# TopSheet_orig.net
KiCad netlist of a schematic drawn in Altium Designer
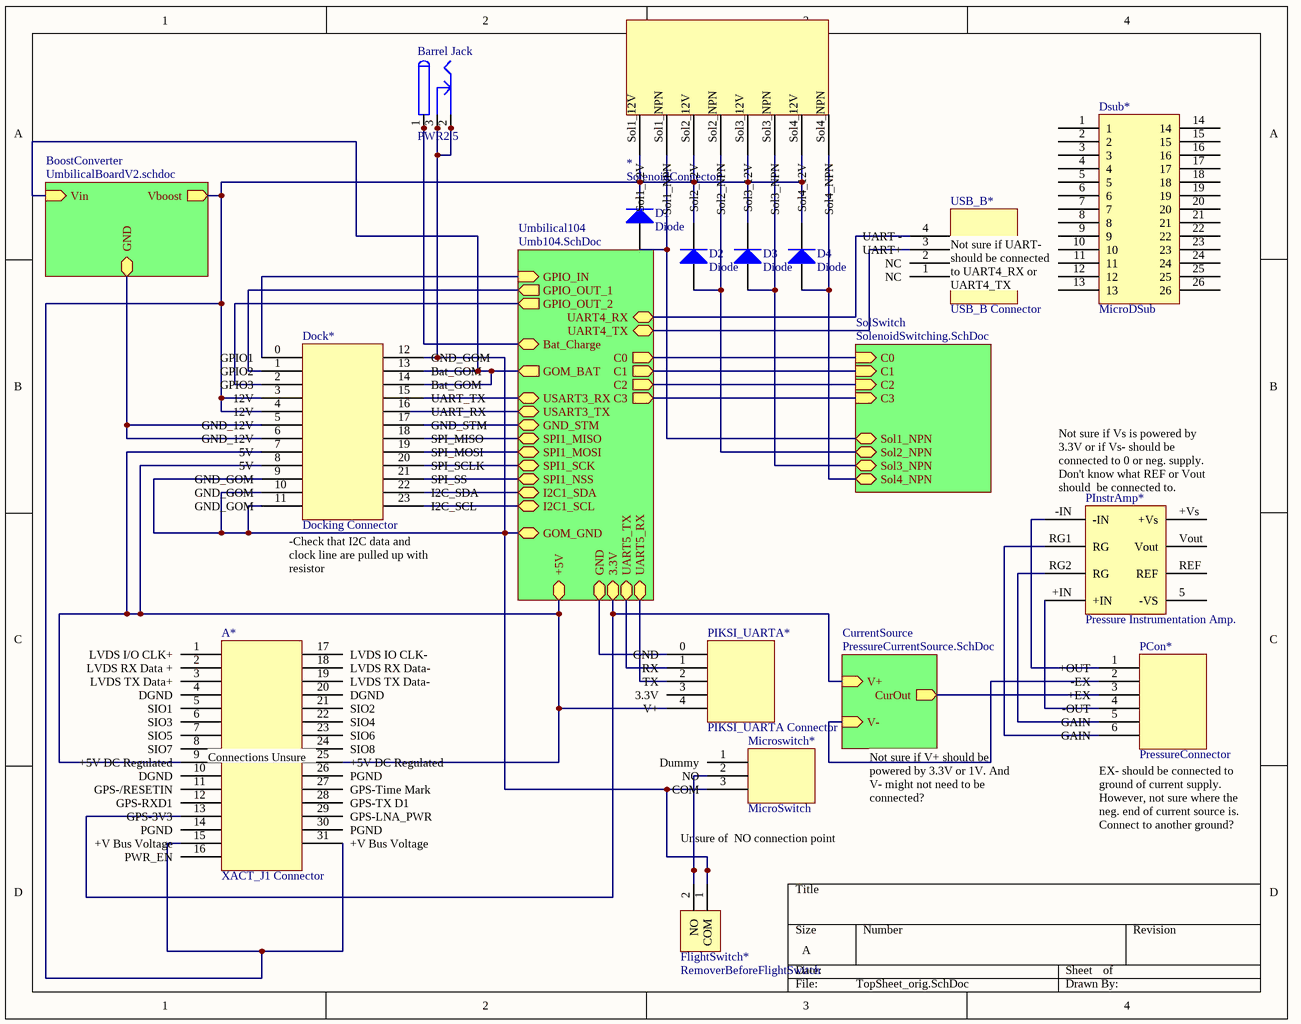
[diagram p0: TopSheet_orig.SchDoc]

(export (version "E")
  (design (tool "Eeschema 10.0.6"))
  (components
    (comp (ref "*")
      (value "SolenoidConnector")
      (footprint "UmbilicalConnectors:Solenoids 8Pin Right Angle")
      (description "Connector for 4 Solenoids")
      (libsource (lib "UmbilicalBoardV2") (part "SolenoidConnector"))
    )
    (comp (ref "A*")
      (value "XACT_J1 Connector")
      (footprint "UmbilicalConnectors:Airborn Nano")
      (description "31 Pin Airborn Nano Connector")
      (libsource (lib "UmbilicalBoardV2") (part "XACT_J1 Connector"))
    )
    (comp (ref "Barrel Jack")
      (value "PWR2.5")
      (footprint "KLD-0202")
      (description "Low Voltage Power Supply Connector")
      (fields (field (name "PUBLISHER") "Altium Limited"))
      (libsource (lib "Miscellaneous Connectors") (part "PWR2.5"))
    )
    (comp (ref "D1")
      (value "Diode")
      (footprint "SMC")
      (description "Default Diode")
      (fields (field (name "PUBLISHER") "Altium Limited"))
      (libsource (lib "Miscellaneous Devices") (part "Diode"))
    )
    (comp (ref "D2")
      (value "Diode")
      (footprint "SMC")
      (description "Default Diode")
      (fields (field (name "PUBLISHER") "Altium Limited"))
      (libsource (lib "Miscellaneous Devices") (part "Diode"))
    )
    (comp (ref "D3")
      (value "Diode")
      (footprint "SMC")
      (description "Default Diode")
      (fields (field (name "PUBLISHER") "Altium Limited"))
      (libsource (lib "Miscellaneous Devices") (part "Diode"))
    )
    (comp (ref "D4")
      (value "Diode")
      (footprint "SMC")
      (description "Default Diode")
      (fields (field (name "PUBLISHER") "Altium Limited"))
      (libsource (lib "Miscellaneous Devices") (part "Diode"))
    )
    (comp (ref "Dock*")
      (value "Docking Connector")
      (footprint "UmbilicalConnectors:Docking Connector")
      (description "24 Pin Connector")
      (libsource (lib "UmbilicalBoardV2") (part "Docking Connector"))
    )
    (comp (ref "Dsub*")
      (value "MicroDSub")
      (footprint "UmbilicalConnectors:MicroDSub")
      (description "12226-5150-00FR")
      (libsource (lib "UmbilicalBoardV2") (part "MicroDSub"))
    )
    (comp (ref "FlightSwitch*")
      (value "RemoverBeforeFlightSwitch")
      (footprint "UmbilicalConnectors:RemoverBeforeFlight Switch")
      (description "53048-0210 Molex Picoblade")
      (libsource (lib "UmbilicalBoardV2") (part "RemoverBeforeFlightSwitch"))
    )
    (comp (ref "Microswitch*")
      (value "MicroSwitch")
      (footprint "UmbilicalConnectors:MicroSwitch_3pin")
      (description "Omron Electronics Inc-EMC Div D2FS-FL-N-A1")
      (libsource (lib "UmbilicalBoardV2") (part "MicroSwitch"))
    )
    (comp (ref "PCon*")
      (value "PressureConnector")
      (footprint "UmbilicalConnectors:Pressure Transducer")
      (description "Molex 70553-0005")
      (libsource (lib "UmbilicalBoardV2") (part "PressureConnector"))
    )
    (comp (ref "PIKSI_UARTA*")
      (value "PIKSI_UARTA Connector")
      (footprint "UmbilicalConnectors:Molex Picoblade 5 Pin")
      (description "Molex Picoblade 5 Pin")
      (libsource (lib "UmbilicalBoardV2") (part "PIKSI_UART Connector"))
    )
    (comp (ref "PInstrAmp*")
      (value "Pressure Instrumentation Amp.")
      (footprint "UmbilicalConnectors:Pressure Instrumentation Amp.")
      (libsource (lib "UmbilicalBoardV2") (part "Pressure Instrumentation Amp."))
    )
    (comp (ref "USB_B*")
      (value "USB_B Connector")
      (footprint "UmbilicalConnectors:USB_B Connector")
      (libsource (lib "UmbilicalBoardV2") (part "USB_B Connector"))
    )
  )
  (nets
    (net (code "3") (name "/Bat_Charge") (class "Default")
      (node (ref "Barrel Jack") (pin "1") (pinfunction "1_1") (pintype "power_in"))
      (node (ref "Barrel Jack") (pin "1A") (pinfunction "1A_1A") (pintype "power_in"))
      (node (ref "Barrel Jack") (pin "1B") (pinfunction "1B_1B") (pintype "power_in"))
    )
    (net (code "13") (name "/GOM_GND") (class "Default")
      (node (ref "Barrel Jack") (pin "2") (pinfunction "2_2") (pintype "power_in"))
      (node (ref "Barrel Jack") (pin "2A") (pinfunction "2A_2A") (pintype "power_in"))
      (node (ref "Barrel Jack") (pin "2B") (pinfunction "2B_2B") (pintype "power_in"))
      (node (ref "Barrel Jack") (pin "3") (pinfunction "3_3") (pintype "power_in"))
      (node (ref "Barrel Jack") (pin "3A") (pinfunction "3A_3A") (pintype "power_in"))
      (node (ref "Barrel Jack") (pin "3B") (pinfunction "3B_3B") (pintype "power_in"))
      (node (ref "FlightSwitch*") (pin "1") (pinfunction "COM_1") (pintype "passive"))
    )
    (net (code "23") (name "/Sol1_NPN") (class "Default")
      (node (ref "D1") (pin "1") (pinfunction "A_1") (pintype "passive"))
    )
    (net (code "24") (name "/Sol2_NPN") (class "Default")
      (node (ref "D2") (pin "1") (pinfunction "A_1") (pintype "passive"))
    )
    (net (code "25") (name "/Sol3_NPN") (class "Default")
      (node (ref "D3") (pin "1") (pinfunction "A_1") (pintype "passive"))
    )
    (net (code "26") (name "/Sol4_NPN") (class "Default")
      (node (ref "D4") (pin "1") (pinfunction "A_1") (pintype "passive"))
    )
    (net (code "34") (name "/Vboost") (class "Default")
      (node (ref "D1") (pin "2") (pinfunction "K_2") (pintype "passive"))
      (node (ref "D2") (pin "2") (pinfunction "K_2") (pintype "passive"))
      (node (ref "D3") (pin "2") (pinfunction "K_2") (pintype "passive"))
      (node (ref "D4") (pin "2") (pinfunction "K_2") (pintype "passive"))
    )
    (net (code "35") (name "unconnected-(*-PadSol1_12V)") (class "Default")
      (node (ref "*") (pin "Sol1_12V") (pinfunction "Sol1_12V_Sol1_12V") (pintype "passive"))
    )
    (net (code "36") (name "unconnected-(*-PadSol1_NPN)") (class "Default")
      (node (ref "*") (pin "Sol1_NPN") (pinfunction "Sol1_NPN_Sol1_NPN") (pintype "passive"))
    )
    (net (code "37") (name "unconnected-(*-PadSol2_12V)") (class "Default")
      (node (ref "*") (pin "Sol2_12V") (pinfunction "Sol2_12V_Sol2_12V") (pintype "passive"))
    )
    (net (code "38") (name "unconnected-(*-PadSol2_NPN)") (class "Default")
      (node (ref "*") (pin "Sol2_NPN") (pinfunction "Sol2_NPN_Sol2_NPN") (pintype "passive"))
    )
    (net (code "39") (name "unconnected-(*-PadSol3_12V)") (class "Default")
      (node (ref "*") (pin "Sol3_12V") (pinfunction "Sol3_12V_Sol3_12V") (pintype "passive"))
    )
    (net (code "40") (name "unconnected-(*-PadSol3_NPN)") (class "Default")
      (node (ref "*") (pin "Sol3_NPN") (pinfunction "Sol3_NPN_Sol3_NPN") (pintype "passive"))
    )
    (net (code "41") (name "unconnected-(*-PadSol4_12V)") (class "Default")
      (node (ref "*") (pin "Sol4_12V") (pinfunction "Sol4_12V_Sol4_12V") (pintype "passive"))
    )
    (net (code "42") (name "unconnected-(*-PadSol4_NPN)") (class "Default")
      (node (ref "*") (pin "Sol4_NPN") (pinfunction "Sol4_NPN_Sol4_NPN") (pintype "passive"))
    )
    (net (code "43") (name "unconnected-(A*-+5V_DC_Regulated-Pad9)") (class "Default")
      (node (ref "A*") (pin "9") (pinfunction "+5V_DC_Regulated_9") (pintype "passive"))
    )
    (net (code "44") (name "unconnected-(A*-+5V_DC_Regulated-Pad25)") (class "Default")
      (node (ref "A*") (pin "25") (pinfunction "+5V_DC_Regulated_25") (pintype "passive"))
    )
    (net (code "45") (name "unconnected-(A*-+V_Bus_Voltage-Pad15)") (class "Default")
      (node (ref "A*") (pin "15") (pinfunction "+V_Bus_Voltage_15") (pintype "passive"))
    )
    (net (code "46") (name "unconnected-(A*-+V_Bus_Voltage-Pad31)") (class "Default")
      (node (ref "A*") (pin "31") (pinfunction "+V_Bus_Voltage_31") (pintype "passive"))
    )
    (net (code "47") (name "unconnected-(A*-DGND-Pad4)") (class "Default")
      (node (ref "A*") (pin "4") (pinfunction "DGND_4") (pintype "passive"))
    )
    (net (code "48") (name "unconnected-(A*-DGND-Pad10)") (class "Default")
      (node (ref "A*") (pin "10") (pinfunction "DGND_10") (pintype "passive"))
    )
    (net (code "49") (name "unconnected-(A*-DGND-Pad20)") (class "Default")
      (node (ref "A*") (pin "20") (pinfunction "DGND_20") (pintype "passive"))
    )
    (net (code "50") (name "unconnected-(A*-GPS-3V3-Pad13)") (class "Default")
      (node (ref "A*") (pin "13") (pinfunction "GPS-3V3_13") (pintype "passive"))
    )
    (net (code "51") (name "unconnected-(A*-GPS-LNA_PWR-Pad29)") (class "Default")
      (node (ref "A*") (pin "29") (pinfunction "GPS-LNA_PWR_29") (pintype "passive"))
    )
    (net (code "52") (name "unconnected-(A*-GPS-RXD1-Pad12)") (class "Default")
      (node (ref "A*") (pin "12") (pinfunction "GPS-RXD1_12") (pintype "passive"))
    )
    (net (code "53") (name "unconnected-(A*-GPS-TX_D1-Pad28)") (class "Default")
      (node (ref "A*") (pin "28") (pinfunction "GPS-TX_D1_28") (pintype "passive"))
    )
    (net (code "54") (name "unconnected-(A*-GPS-Time_Mark-Pad27)") (class "Default")
      (node (ref "A*") (pin "27") (pinfunction "GPS-Time_Mark_27") (pintype "passive"))
    )
    (net (code "55") (name "unconnected-(A*-GPS-{slash}RESETIN-Pad11)") (class "Default")
      (node (ref "A*") (pin "11") (pinfunction "GPS-/RESETIN_11") (pintype "passive"))
    )
    (net (code "56") (name "unconnected-(A*-LVDS_IO_CLK--Pad17)") (class "Default")
      (node (ref "A*") (pin "17") (pinfunction "LVDS_IO_CLK-_17") (pintype "passive"))
    )
    (net (code "57") (name "unconnected-(A*-LVDS_I{slash}O_CLK+-Pad1)") (class "Default")
      (node (ref "A*") (pin "1") (pinfunction "LVDS_I/O_CLK+_1") (pintype "passive"))
    )
    (net (code "58") (name "unconnected-(A*-LVDS_RX_Data--Pad18)") (class "Default")
      (node (ref "A*") (pin "18") (pinfunction "LVDS_RX_Data-_18") (pintype "passive"))
    )
    (net (code "59") (name "unconnected-(A*-LVDS_RX_Data_+-Pad2)") (class "Default")
      (node (ref "A*") (pin "2") (pinfunction "LVDS_RX_Data_+_2") (pintype "passive"))
    )
    (net (code "60") (name "unconnected-(A*-LVDS_TX_Data+-Pad3)") (class "Default")
      (node (ref "A*") (pin "3") (pinfunction "LVDS_TX_Data+_3") (pintype "passive"))
    )
    (net (code "61") (name "unconnected-(A*-LVDS_TX_Data--Pad19)") (class "Default")
      (node (ref "A*") (pin "19") (pinfunction "LVDS_TX_Data-_19") (pintype "passive"))
    )
    (net (code "62") (name "unconnected-(A*-PGND-Pad14)") (class "Default")
      (node (ref "A*") (pin "14") (pinfunction "PGND_14") (pintype "passive"))
    )
    (net (code "63") (name "unconnected-(A*-PGND-Pad26)") (class "Default")
      (node (ref "A*") (pin "26") (pinfunction "PGND_26") (pintype "passive"))
    )
    (net (code "64") (name "unconnected-(A*-PGND-Pad30)") (class "Default")
      (node (ref "A*") (pin "30") (pinfunction "PGND_30") (pintype "passive"))
    )
    (net (code "65") (name "unconnected-(A*-PWR_EN-Pad16)") (class "Default")
      (node (ref "A*") (pin "16") (pinfunction "PWR_EN_16") (pintype "passive"))
    )
    (net (code "66") (name "unconnected-(A*-SIO1-Pad5)") (class "Default")
      (node (ref "A*") (pin "5") (pinfunction "SIO1_5") (pintype "passive"))
    )
    (net (code "67") (name "unconnected-(A*-SIO2-Pad21)") (class "Default")
      (node (ref "A*") (pin "21") (pinfunction "SIO2_21") (pintype "passive"))
    )
    (net (code "68") (name "unconnected-(A*-SIO3-Pad6)") (class "Default")
      (node (ref "A*") (pin "6") (pinfunction "SIO3_6") (pintype "passive"))
    )
    (net (code "69") (name "unconnected-(A*-SIO4-Pad22)") (class "Default")
      (node (ref "A*") (pin "22") (pinfunction "SIO4_22") (pintype "passive"))
    )
    (net (code "70") (name "unconnected-(A*-SIO5-Pad7)") (class "Default")
      (node (ref "A*") (pin "7") (pinfunction "SIO5_7") (pintype "passive"))
    )
    (net (code "71") (name "unconnected-(A*-SIO6-Pad23)") (class "Default")
      (node (ref "A*") (pin "23") (pinfunction "SIO6_23") (pintype "passive"))
    )
    (net (code "72") (name "unconnected-(A*-SIO7-Pad8)") (class "Default")
      (node (ref "A*") (pin "8") (pinfunction "SIO7_8") (pintype "passive"))
    )
    (net (code "73") (name "unconnected-(A*-SIO8-Pad24)") (class "Default")
      (node (ref "A*") (pin "24") (pinfunction "SIO8_24") (pintype "passive"))
    )
    (net (code "74") (name "unconnected-(Dock*-5V-Pad7)") (class "Default")
      (node (ref "Dock*") (pin "7") (pinfunction "5V_7") (pintype "passive"))
    )
    (net (code "75") (name "unconnected-(Dock*-5V-Pad8)") (class "Default")
      (node (ref "Dock*") (pin "8") (pinfunction "5V_8") (pintype "passive"))
    )
    (net (code "76") (name "unconnected-(Dock*-12V-Pad3)") (class "Default")
      (node (ref "Dock*") (pin "3") (pinfunction "12V_3") (pintype "passive"))
    )
    (net (code "77") (name "unconnected-(Dock*-12V-Pad4)") (class "Default")
      (node (ref "Dock*") (pin "4") (pinfunction "12V_4") (pintype "passive"))
    )
    (net (code "78") (name "unconnected-(Dock*-Bat_GOM-Pad13)") (class "Default")
      (node (ref "Dock*") (pin "13") (pinfunction "Bat_GOM_13") (pintype "passive"))
    )
    (net (code "79") (name "unconnected-(Dock*-Bat_GOM-Pad14)") (class "Default")
      (node (ref "Dock*") (pin "14") (pinfunction "Bat_GOM_14") (pintype "passive"))
    )
    (net (code "80") (name "unconnected-(Dock*-GND_12V-Pad5)") (class "Default")
      (node (ref "Dock*") (pin "5") (pinfunction "GND_12V_5") (pintype "passive"))
    )
    (net (code "81") (name "unconnected-(Dock*-GND_12V-Pad6)") (class "Default")
      (node (ref "Dock*") (pin "6") (pinfunction "GND_12V_6") (pintype "passive"))
    )
    (net (code "82") (name "unconnected-(Dock*-GND_GOM-Pad9)") (class "Default")
      (node (ref "Dock*") (pin "9") (pinfunction "GND_GOM_9") (pintype "passive"))
    )
    (net (code "83") (name "unconnected-(Dock*-GND_GOM-Pad10)") (class "Default")
      (node (ref "Dock*") (pin "10") (pinfunction "GND_GOM_10") (pintype "passive"))
    )
    (net (code "84") (name "unconnected-(Dock*-GND_GOM-Pad11)") (class "Default")
      (node (ref "Dock*") (pin "11") (pinfunction "GND_GOM_11") (pintype "passive"))
    )
    (net (code "85") (name "unconnected-(Dock*-GND_GOM-Pad12)") (class "Default")
      (node (ref "Dock*") (pin "12") (pinfunction "GND_GOM_12") (pintype "passive"))
    )
    (net (code "86") (name "unconnected-(Dock*-GND_STM-Pad17)") (class "Default")
      (node (ref "Dock*") (pin "17") (pinfunction "GND_STM_17") (pintype "passive"))
    )
    (net (code "87") (name "unconnected-(Dock*-GPIO1-Pad0)") (class "Default")
      (node (ref "Dock*") (pin "0") (pinfunction "GPIO1_0") (pintype "passive"))
    )
    (net (code "88") (name "unconnected-(Dock*-GPIO2-Pad1)") (class "Default")
      (node (ref "Dock*") (pin "1") (pinfunction "GPIO2_1") (pintype "passive"))
    )
    (net (code "89") (name "unconnected-(Dock*-GPIO3-Pad2)") (class "Default")
      (node (ref "Dock*") (pin "2") (pinfunction "GPIO3_2") (pintype "passive"))
    )
    (net (code "90") (name "unconnected-(Dock*-I2C_SCL-Pad23)") (class "Default")
      (node (ref "Dock*") (pin "23") (pinfunction "I2C_SCL_23") (pintype "passive"))
    )
    (net (code "91") (name "unconnected-(Dock*-I2C_SDA-Pad22)") (class "Default")
      (node (ref "Dock*") (pin "22") (pinfunction "I2C_SDA_22") (pintype "passive"))
    )
    (net (code "92") (name "unconnected-(Dock*-SPI_MISO-Pad18)") (class "Default")
      (node (ref "Dock*") (pin "18") (pinfunction "SPI_MISO_18") (pintype "passive"))
    )
    (net (code "93") (name "unconnected-(Dock*-SPI_MOSI-Pad19)") (class "Default")
      (node (ref "Dock*") (pin "19") (pinfunction "SPI_MOSI_19") (pintype "passive"))
    )
    (net (code "94") (name "unconnected-(Dock*-SPI_SCLK-Pad20)") (class "Default")
      (node (ref "Dock*") (pin "20") (pinfunction "SPI_SCLK_20") (pintype "passive"))
    )
    (net (code "95") (name "unconnected-(Dock*-SPI_SS-Pad21)") (class "Default")
      (node (ref "Dock*") (pin "21") (pinfunction "SPI_SS_21") (pintype "passive"))
    )
    (net (code "96") (name "unconnected-(Dock*-UART_RX-Pad16)") (class "Default")
      (node (ref "Dock*") (pin "16") (pinfunction "UART_RX_16") (pintype "passive"))
    )
    (net (code "97") (name "unconnected-(Dock*-UART_TX-Pad15)") (class "Default")
      (node (ref "Dock*") (pin "15") (pinfunction "UART_TX_15") (pintype "passive"))
    )
    (net (code "98") (name "unconnected-(Dsub*-Pad1)") (class "Default")
      (node (ref "Dsub*") (pin "1") (pinfunction "1_1") (pintype "passive"))
    )
    (net (code "99") (name "unconnected-(Dsub*-Pad2)") (class "Default")
      (node (ref "Dsub*") (pin "2") (pinfunction "2_2") (pintype "passive"))
    )
    (net (code "100") (name "unconnected-(Dsub*-Pad3)") (class "Default")
      (node (ref "Dsub*") (pin "3") (pinfunction "3_3") (pintype "passive"))
    )
    (net (code "101") (name "unconnected-(Dsub*-Pad4)") (class "Default")
      (node (ref "Dsub*") (pin "4") (pinfunction "4_4") (pintype "passive"))
    )
    (net (code "102") (name "unconnected-(Dsub*-Pad5)") (class "Default")
      (node (ref "Dsub*") (pin "5") (pinfunction "5_5") (pintype "passive"))
    )
    (net (code "103") (name "unconnected-(Dsub*-Pad6)") (class "Default")
      (node (ref "Dsub*") (pin "6") (pinfunction "6_6") (pintype "passive"))
    )
    (net (code "104") (name "unconnected-(Dsub*-Pad7)") (class "Default")
      (node (ref "Dsub*") (pin "7") (pinfunction "7_7") (pintype "passive"))
    )
    (net (code "105") (name "unconnected-(Dsub*-Pad8)") (class "Default")
      (node (ref "Dsub*") (pin "8") (pinfunction "8_8") (pintype "passive"))
    )
    (net (code "106") (name "unconnected-(Dsub*-Pad9)") (class "Default")
      (node (ref "Dsub*") (pin "9") (pinfunction "9_9") (pintype "passive"))
    )
    (net (code "107") (name "unconnected-(Dsub*-Pad10)") (class "Default")
      (node (ref "Dsub*") (pin "10") (pinfunction "10_10") (pintype "passive"))
    )
    (net (code "108") (name "unconnected-(Dsub*-Pad11)") (class "Default")
      (node (ref "Dsub*") (pin "11") (pinfunction "11_11") (pintype "passive"))
    )
    (net (code "109") (name "unconnected-(Dsub*-Pad12)") (class "Default")
      (node (ref "Dsub*") (pin "12") (pinfunction "12_12") (pintype "passive"))
    )
    (net (code "110") (name "unconnected-(Dsub*-Pad13)") (class "Default")
      (node (ref "Dsub*") (pin "13") (pinfunction "13_13") (pintype "passive"))
    )
    (net (code "111") (name "unconnected-(Dsub*-Pad14)") (class "Default")
      (node (ref "Dsub*") (pin "14") (pinfunction "14_14") (pintype "passive"))
    )
    (net (code "112") (name "unconnected-(Dsub*-Pad15)") (class "Default")
      (node (ref "Dsub*") (pin "15") (pinfunction "15_15") (pintype "passive"))
    )
    (net (code "113") (name "unconnected-(Dsub*-Pad16)") (class "Default")
      (node (ref "Dsub*") (pin "16") (pinfunction "16_16") (pintype "passive"))
    )
    (net (code "114") (name "unconnected-(Dsub*-Pad17)") (class "Default")
      (node (ref "Dsub*") (pin "17") (pinfunction "17_17") (pintype "passive"))
    )
    (net (code "115") (name "unconnected-(Dsub*-Pad18)") (class "Default")
      (node (ref "Dsub*") (pin "18") (pinfunction "18_18") (pintype "passive"))
    )
    (net (code "116") (name "unconnected-(Dsub*-Pad19)") (class "Default")
      (node (ref "Dsub*") (pin "19") (pinfunction "19_19") (pintype "passive"))
    )
    (net (code "117") (name "unconnected-(Dsub*-Pad20)") (class "Default")
      (node (ref "Dsub*") (pin "20") (pinfunction "20_20") (pintype "passive"))
    )
    (net (code "118") (name "unconnected-(Dsub*-Pad21)") (class "Default")
      (node (ref "Dsub*") (pin "21") (pinfunction "21_21") (pintype "passive"))
    )
    (net (code "119") (name "unconnected-(Dsub*-Pad22)") (class "Default")
      (node (ref "Dsub*") (pin "22") (pinfunction "22_22") (pintype "passive"))
    )
    (net (code "120") (name "unconnected-(Dsub*-Pad23)") (class "Default")
      (node (ref "Dsub*") (pin "23") (pinfunction "23_23") (pintype "passive"))
    )
    (net (code "121") (name "unconnected-(Dsub*-Pad24)") (class "Default")
      (node (ref "Dsub*") (pin "24") (pinfunction "24_24") (pintype "passive"))
    )
    (net (code "122") (name "unconnected-(Dsub*-Pad25)") (class "Default")
      (node (ref "Dsub*") (pin "25") (pinfunction "25_25") (pintype "passive"))
    )
    (net (code "123") (name "unconnected-(Dsub*-Pad26)") (class "Default")
      (node (ref "Dsub*") (pin "26") (pinfunction "26_26") (pintype "passive"))
    )
    (net (code "124") (name "unconnected-(FlightSwitch*-NO-Pad2)") (class "Default")
      (node (ref "FlightSwitch*") (pin "2") (pinfunction "NO_2") (pintype "passive"))
    )
    (net (code "125") (name "unconnected-(Microswitch*-COM-Pad3)") (class "Default")
      (node (ref "Microswitch*") (pin "3") (pinfunction "COM_3") (pintype "passive"))
    )
    (net (code "126") (name "unconnected-(Microswitch*-Dummy-Pad1)") (class "Default")
      (node (ref "Microswitch*") (pin "1") (pinfunction "Dummy_1") (pintype "passive"))
    )
    (net (code "127") (name "unconnected-(Microswitch*-NO-Pad2)") (class "Default")
      (node (ref "Microswitch*") (pin "2") (pinfunction "NO_2") (pintype "passive"))
    )
    (net (code "128") (name "unconnected-(PCon*-+EX-Pad3)") (class "Default")
      (node (ref "PCon*") (pin "3") (pinfunction "+EX_3") (pintype "passive"))
    )
    (net (code "129") (name "unconnected-(PCon*-+OUT-Pad1)") (class "Default")
      (node (ref "PCon*") (pin "1") (pinfunction "+OUT_1") (pintype "passive"))
    )
    (net (code "130") (name "unconnected-(PCon*--EX-Pad2)") (class "Default")
      (node (ref "PCon*") (pin "2") (pinfunction "-EX_2") (pintype "passive"))
    )
    (net (code "131") (name "unconnected-(PCon*--OUT-Pad4)") (class "Default")
      (node (ref "PCon*") (pin "4") (pinfunction "-OUT_4") (pintype "passive"))
    )
    (net (code "132") (name "unconnected-(PCon*-GAIN-Pad5)") (class "Default")
      (node (ref "PCon*") (pin "5") (pinfunction "GAIN_5") (pintype "passive"))
    )
    (net (code "133") (name "unconnected-(PCon*-GAIN-Pad6)") (class "Default")
      (node (ref "PCon*") (pin "6") (pinfunction "GAIN_6") (pintype "passive"))
    )
    (net (code "134") (name "unconnected-(PIKSI_UARTA*-3.3V-Pad3)") (class "Default")
      (node (ref "PIKSI_UARTA*") (pin "3") (pinfunction "3.3V_3") (pintype "passive"))
    )
    (net (code "135") (name "unconnected-(PIKSI_UARTA*-GND-Pad0)") (class "Default")
      (node (ref "PIKSI_UARTA*") (pin "0") (pinfunction "GND_0") (pintype "passive"))
    )
    (net (code "136") (name "unconnected-(PIKSI_UARTA*-RX-Pad1)") (class "Default")
      (node (ref "PIKSI_UARTA*") (pin "1") (pinfunction "RX_1") (pintype "passive"))
    )
    (net (code "137") (name "unconnected-(PIKSI_UARTA*-TX-Pad2)") (class "Default")
      (node (ref "PIKSI_UARTA*") (pin "2") (pinfunction "TX_2") (pintype "passive"))
    )
    (net (code "138") (name "unconnected-(PIKSI_UARTA*-V+-Pad4)") (class "Default")
      (node (ref "PIKSI_UARTA*") (pin "4") (pinfunction "V+_4") (pintype "passive"))
    )
    (net (code "139") (name "unconnected-(PInstrAmp*--VS-Pad5)") (class "Default")
      (node (ref "PInstrAmp*") (pin "5") (pinfunction "-VS_5") (pintype "passive"))
    )
    (net (code "140") (name "unconnected-(PInstrAmp*-Pad+IN)") (class "Default")
      (node (ref "PInstrAmp*") (pin "+IN") (pinfunction "+IN_+IN") (pintype "passive"))
    )
    (net (code "141") (name "unconnected-(PInstrAmp*-Pad+Vs)") (class "Default")
      (node (ref "PInstrAmp*") (pin "+Vs") (pinfunction "+Vs_+Vs") (pintype "passive"))
    )
    (net (code "142") (name "unconnected-(PInstrAmp*-Pad-IN)") (class "Default")
      (node (ref "PInstrAmp*") (pin "-IN") (pinfunction "-IN_-IN") (pintype "passive"))
    )
    (net (code "143") (name "unconnected-(PInstrAmp*-PadREF)") (class "Default")
      (node (ref "PInstrAmp*") (pin "REF") (pinfunction "REF_REF") (pintype "passive"))
    )
    (net (code "144") (name "unconnected-(PInstrAmp*-PadVout)") (class "Default")
      (node (ref "PInstrAmp*") (pin "Vout") (pinfunction "Vout_Vout") (pintype "passive"))
    )
    (net (code "145") (name "unconnected-(PInstrAmp*-RG-PadRG1)") (class "Default")
      (node (ref "PInstrAmp*") (pin "RG1") (pinfunction "RG_RG1") (pintype "passive"))
    )
    (net (code "146") (name "unconnected-(PInstrAmp*-RG-PadRG2)") (class "Default")
      (node (ref "PInstrAmp*") (pin "RG2") (pinfunction "RG_RG2") (pintype "passive"))
    )
    (net (code "147") (name "unconnected-(USB_B*-NC-Pad1)") (class "Default")
      (node (ref "USB_B*") (pin "1") (pinfunction "NC_1") (pintype "passive"))
    )
    (net (code "148") (name "unconnected-(USB_B*-NC-Pad2)") (class "Default")
      (node (ref "USB_B*") (pin "2") (pinfunction "NC_2") (pintype "passive"))
    )
    (net (code "149") (name "unconnected-(USB_B*-UART+-Pad3)") (class "Default")
      (node (ref "USB_B*") (pin "3") (pinfunction "UART+_3") (pintype "passive"))
    )
    (net (code "150") (name "unconnected-(USB_B*-UART_--Pad4)") (class "Default")
      (node (ref "USB_B*") (pin "4") (pinfunction "UART_-_4") (pintype "passive"))
    )
  )
)
